# design.net
KiCad netlist of a schematic drawn in Altium Designer
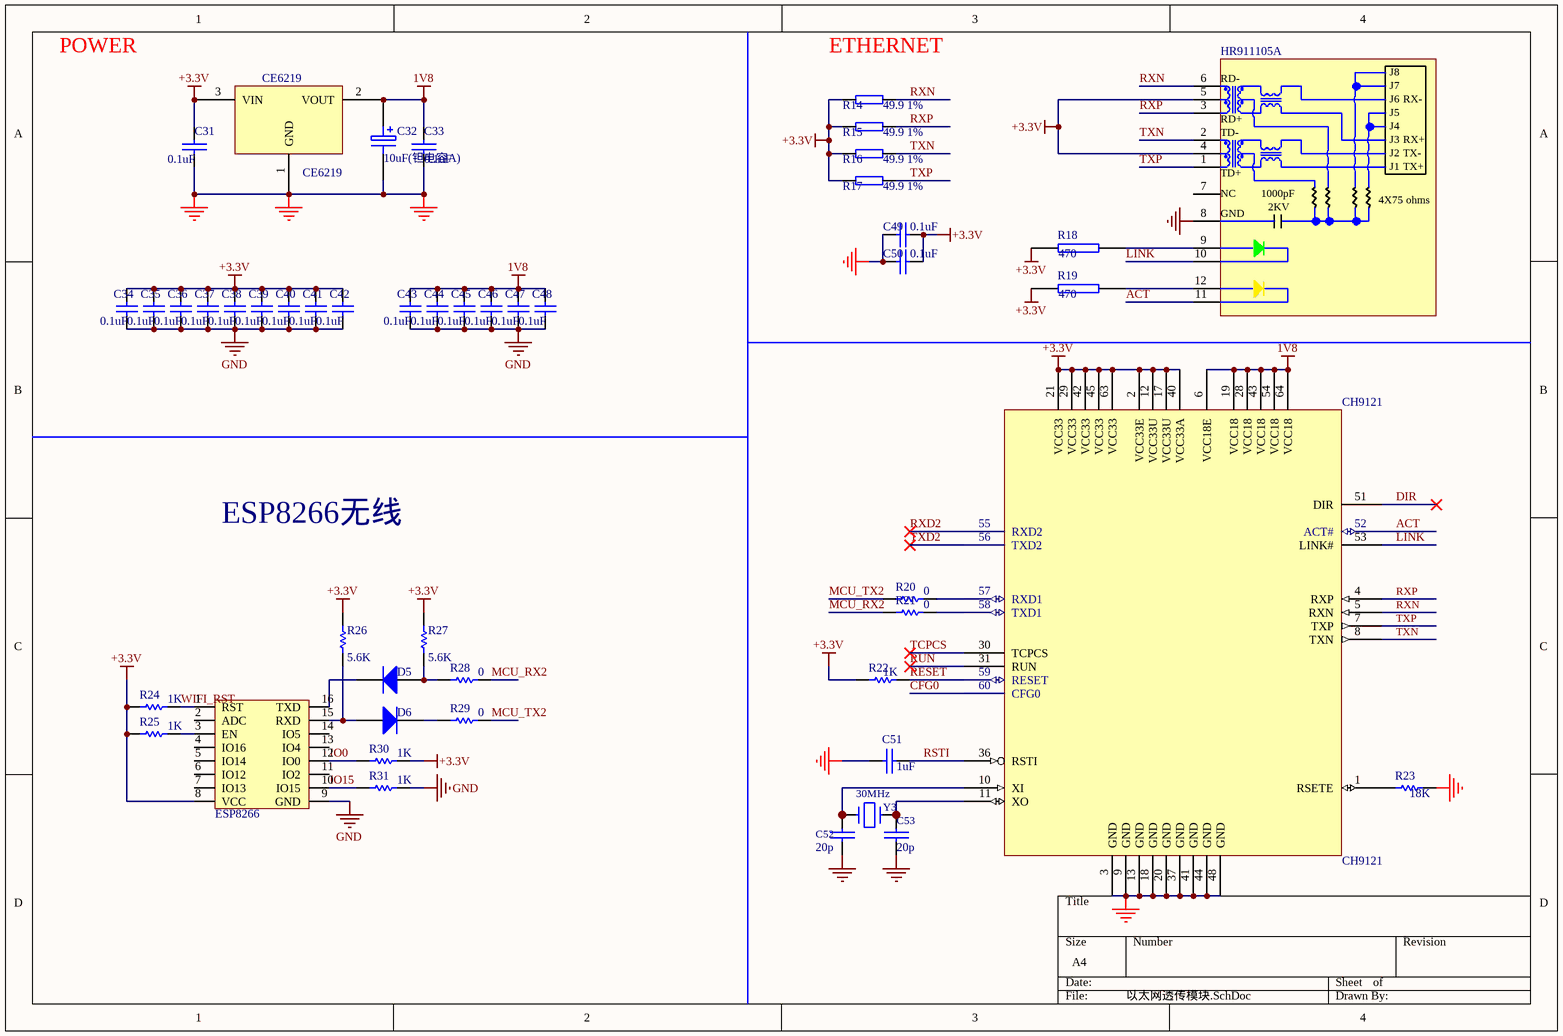
[diagram p0: 以太网透传模块.SchDoc]

(export (version "E")
  (design (tool "Eeschema 10.0.6"))
  (components
    (comp (ref "C31")
      (value "104")
      (footprint "0603")
      (description "Capacitor")
      (fields (field (name "ALTIUM_UNNAMED_1") "0.1uF"))
      (libsource (lib "*") (part "CAP"))
    )
    (comp (ref "C32")
      (value "10uF(钽电容A)")
      (footprint "钽电容(A)")
      (description "Electrolytic Capacitor")
      (libsource (lib "*") (part "ELECTRO1"))
    )
    (comp (ref "C33")
      (value "104")
      (footprint "0603")
      (description "Capacitor")
      (fields (field (name "ALTIUM_UNNAMED_1") "0.1uF"))
      (libsource (lib "*") (part "CAP"))
    )
    (comp (ref "C34")
      (value "0.1uF")
      (footprint "0603")
      (description "Capacitor")
      (fields (field (name "Comment") "104") (field (name "PUBLISHER") "Altium Limited"))
      (libsource (lib "Miscellaneous Devices") (part "Cap"))
    )
    (comp (ref "C35")
      (value "0.1uF")
      (footprint "0603")
      (description "Capacitor")
      (fields (field (name "Comment") "104") (field (name "PUBLISHER") "Altium Limited"))
      (libsource (lib "Miscellaneous Devices") (part "Cap"))
    )
    (comp (ref "C36")
      (value "0.1uF")
      (footprint "0603")
      (description "Capacitor")
      (fields (field (name "Comment") "104") (field (name "PUBLISHER") "Altium Limited"))
      (libsource (lib "Miscellaneous Devices") (part "Cap"))
    )
    (comp (ref "C37")
      (value "0.1uF")
      (footprint "0603")
      (description "Capacitor")
      (fields (field (name "Comment") "104") (field (name "PUBLISHER") "Altium Limited"))
      (libsource (lib "Miscellaneous Devices") (part "Cap"))
    )
    (comp (ref "C38")
      (value "0.1uF")
      (footprint "0603")
      (description "Capacitor")
      (fields (field (name "Comment") "104") (field (name "PUBLISHER") "Altium Limited"))
      (libsource (lib "Miscellaneous Devices") (part "Cap"))
    )
    (comp (ref "C39")
      (value "0.1uF")
      (footprint "0603")
      (description "Capacitor")
      (fields (field (name "Comment") "104") (field (name "PUBLISHER") "Altium Limited"))
      (libsource (lib "Miscellaneous Devices") (part "Cap"))
    )
    (comp (ref "C40")
      (value "0.1uF")
      (footprint "0603")
      (description "Capacitor")
      (fields (field (name "Comment") "104") (field (name "PUBLISHER") "Altium Limited"))
      (libsource (lib "Miscellaneous Devices") (part "Cap"))
    )
    (comp (ref "C41")
      (value "0.1uF")
      (footprint "0603")
      (description "Capacitor")
      (fields (field (name "Comment") "104") (field (name "PUBLISHER") "Altium Limited"))
      (libsource (lib "Miscellaneous Devices") (part "Cap"))
    )
    (comp (ref "C42")
      (value "0.1uF")
      (footprint "0603")
      (description "Capacitor")
      (fields (field (name "Comment") "104") (field (name "PUBLISHER") "Altium Limited"))
      (libsource (lib "Miscellaneous Devices") (part "Cap"))
    )
    (comp (ref "C43")
      (value "0.1uF")
      (footprint "0603")
      (description "Capacitor")
      (fields (field (name "Comment") "104") (field (name "PUBLISHER") "Altium Limited"))
      (libsource (lib "Miscellaneous Devices") (part "Cap"))
    )
    (comp (ref "C44")
      (value "0.1uF")
      (footprint "0603")
      (description "Capacitor")
      (fields (field (name "Comment") "104") (field (name "PUBLISHER") "Altium Limited"))
      (libsource (lib "Miscellaneous Devices") (part "Cap"))
    )
    (comp (ref "C45")
      (value "0.1uF")
      (footprint "0603")
      (description "Capacitor")
      (fields (field (name "Comment") "104") (field (name "PUBLISHER") "Altium Limited"))
      (libsource (lib "Miscellaneous Devices") (part "Cap"))
    )
    (comp (ref "C46")
      (value "0.1uF")
      (footprint "0603")
      (description "Capacitor")
      (fields (field (name "Comment") "104") (field (name "PUBLISHER") "Altium Limited"))
      (libsource (lib "Miscellaneous Devices") (part "Cap"))
    )
    (comp (ref "C47")
      (value "0.1uF")
      (footprint "0603")
      (description "Capacitor")
      (fields (field (name "Comment") "104") (field (name "PUBLISHER") "Altium Limited"))
      (libsource (lib "Miscellaneous Devices") (part "Cap"))
    )
    (comp (ref "C48")
      (value "0.1uF")
      (footprint "0603")
      (description "Capacitor")
      (fields (field (name "Comment") "104") (field (name "PUBLISHER") "Altium Limited"))
      (libsource (lib "Miscellaneous Devices") (part "Cap"))
    )
    (comp (ref "C49")
      (value "104")
      (footprint "0603")
      (description "Capacitor")
      (fields (field (name "ALTIUM_UNNAMED_1") "0.1uF"))
      (libsource (lib "*") (part "CAP"))
    )
    (comp (ref "C50")
      (value "104")
      (footprint "0603")
      (description "Capacitor")
      (fields (field (name "ALTIUM_UNNAMED_1") "0.1uF"))
      (libsource (lib "*") (part "CAP"))
    )
    (comp (ref "C51")
      (value "105")
      (footprint "0603")
      (description "Capacitor")
      (fields (field (name "ALTIUM_UNNAMED_1") "1uF"))
      (libsource (lib "*") (part "CAP"))
    )
    (comp (ref "C52")
      (value "20")
      (footprint "0603")
      (fields (field (name "ALTIUM_UNNAMED_1") "20p"))
      (libsource (lib "*") (part "Pro1BB.tmp_20p_7"))
    )
    (comp (ref "C53")
      (value "20")
      (footprint "0603")
      (fields (field (name "ALTIUM_UNNAMED_1") "20p"))
      (libsource (lib "*") (part "Pro1BB.tmp_20p_7"))
    )
    (comp (ref "CE6219") (value "CE6219") (footprint "SOT-23") (libsource (lib "*") (part "LM1117_3.3V")))
    (comp (ref "CH9121") (value "CH9121") (footprint "LQFP64_10x10") (libsource (lib "*") (part "CH9121")))
    (comp (ref "D5")
      (value "IN5819")
      (footprint "SOD-123")
      (description "1 Amp General Purpose Rectifier")
      (fields (field (name "PUBLISHER") "Altium Limited"))
      (libsource (lib "Miscellaneous Devices") (part "Diode 1N4001"))
    )
    (comp (ref "D6")
      (value "IN5819")
      (footprint "SOD-123")
      (description "1 Amp General Purpose Rectifier")
      (fields (field (name "PUBLISHER") "Altium Limited"))
      (libsource (lib "Miscellaneous Devices") (part "Diode 1N4001"))
    )
    (comp (ref "ESP8266")
      (value "ESP8266")
      (footprint "ESP8266")
      (libsource (lib "智能柜控制模块") (part "ESP8266"))
    )
    (comp (ref "HR911105A")
      (value "HR911105A")
      (footprint "HR911105A")
      (libsource (lib "*") (part "HR911105A"))
    )
    (comp (ref "R14")
      (value "49.9 1%")
      (footprint "0603")
      (fields (field (name "ALTIUM_UNNAMED_1") "49.9 1%"))
      (libsource (lib "*") (part "DZ"))
    )
    (comp (ref "R15")
      (value "49.9 1%")
      (footprint "0603")
      (fields (field (name "ALTIUM_UNNAMED_1") "49.9 1%"))
      (libsource (lib "*") (part "DZ"))
    )
    (comp (ref "R16")
      (value "49.9 1%")
      (footprint "0603")
      (fields (field (name "ALTIUM_UNNAMED_1") "49.9 1%"))
      (libsource (lib "*") (part "DZ"))
    )
    (comp (ref "R17")
      (value "49.9 1%")
      (footprint "0603")
      (fields (field (name "ALTIUM_UNNAMED_1") "49.9 1%"))
      (libsource (lib "*") (part "DZ"))
    )
    (comp (ref "R18")
      (value "470")
      (footprint "0603")
      (fields (field (name "ALTIUM_UNNAMED_1") "470"))
      (libsource (lib "*") (part "RES2"))
    )
    (comp (ref "R19")
      (value "470")
      (footprint "0603")
      (fields (field (name "ALTIUM_UNNAMED_1") "470"))
      (libsource (lib "*") (part "RES2"))
    )
    (comp (ref "R20")
      (value "0")
      (footprint "0603")
      (description "Resistor")
      (fields (field (name "PUBLISHER") "Altium Limited"))
      (libsource (lib "Miscellaneous Devices") (part "Res1"))
    )
    (comp (ref "R21")
      (value "0")
      (footprint "0603")
      (description "Resistor")
      (fields (field (name "PUBLISHER") "Altium Limited"))
      (libsource (lib "Miscellaneous Devices") (part "Res1"))
    )
    (comp (ref "R22")
      (value "1K")
      (footprint "0603")
      (description "Resistor")
      (fields (field (name "PUBLISHER") "Altium Limited"))
      (libsource (lib "Miscellaneous Devices") (part "Res1"))
    )
    (comp (ref "R23")
      (value "18K")
      (footprint "0603")
      (description "Resistor")
      (fields (field (name "PUBLISHER") "Altium Limited"))
      (libsource (lib "Miscellaneous Devices") (part "Res1"))
    )
    (comp (ref "R24")
      (value "1K")
      (footprint "0603")
      (description "Resistor")
      (fields (field (name "PUBLISHER") "Altium Limited"))
      (libsource (lib "Miscellaneous Devices") (part "Res1"))
    )
    (comp (ref "R25")
      (value "1K")
      (footprint "0603")
      (description "Resistor")
      (fields (field (name "PUBLISHER") "Altium Limited"))
      (libsource (lib "Miscellaneous Devices") (part "Res1"))
    )
    (comp (ref "R26")
      (value "5.6K")
      (footprint "0603")
      (description "Resistor")
      (fields (field (name "PUBLISHER") "Altium Limited"))
      (libsource (lib "Miscellaneous Devices") (part "Res1"))
    )
    (comp (ref "R27")
      (value "5.6K")
      (footprint "0603")
      (description "Resistor")
      (fields (field (name "PUBLISHER") "Altium Limited"))
      (libsource (lib "Miscellaneous Devices") (part "Res1"))
    )
    (comp (ref "R28")
      (value "0")
      (footprint "0603")
      (description "Resistor")
      (fields (field (name "PUBLISHER") "Altium Limited"))
      (libsource (lib "Miscellaneous Devices") (part "Res1"))
    )
    (comp (ref "R29")
      (value "0")
      (footprint "0603")
      (description "Resistor")
      (fields (field (name "PUBLISHER") "Altium Limited"))
      (libsource (lib "Miscellaneous Devices") (part "Res1"))
    )
    (comp (ref "R30")
      (value "1K")
      (footprint "0603")
      (description "Resistor")
      (fields (field (name "PUBLISHER") "Altium Limited"))
      (libsource (lib "Miscellaneous Devices") (part "Res1"))
    )
    (comp (ref "R31")
      (value "1K")
      (footprint "0603")
      (description "Resistor")
      (fields (field (name "PUBLISHER") "Altium Limited"))
      (libsource (lib "Miscellaneous Devices") (part "Res1"))
    )
    (comp (ref "Y3") (value "30MHz") (footprint "4025") (libsource (lib "*") (part "Pro1BB.tmp_12MHz_6")))
  )
  (nets
    (net (code "1") (name "+3.3V") (class "Default")
      (node (ref "C31") (pin "1") (pinfunction "1_1") (pintype "passive"))
      (node (ref "C34") (pin "1") (pinfunction "1_1") (pintype "passive"))
      (node (ref "C35") (pin "1") (pinfunction "1_1") (pintype "passive"))
      (node (ref "C36") (pin "1") (pinfunction "1_1") (pintype "passive"))
      (node (ref "C37") (pin "1") (pinfunction "1_1") (pintype "passive"))
      (node (ref "C38") (pin "1") (pinfunction "1_1") (pintype "passive"))
      (node (ref "C39") (pin "1") (pinfunction "1_1") (pintype "passive"))
      (node (ref "C40") (pin "1") (pinfunction "1_1") (pintype "passive"))
      (node (ref "C41") (pin "1") (pinfunction "1_1") (pintype "passive"))
      (node (ref "C42") (pin "1") (pinfunction "1_1") (pintype "passive"))
      (node (ref "C49") (pin "1") (pinfunction "1_1") (pintype "passive"))
      (node (ref "C50") (pin "1") (pinfunction "1_1") (pintype "passive"))
      (node (ref "CE6219") (pin "3") (pinfunction "VIN_3") (pintype "passive"))
      (node (ref "CH9121") (pin "12") (pinfunction "VCC33U_12") (pintype "power_in"))
      (node (ref "CH9121") (pin "17") (pinfunction "VCC33U_17") (pintype "power_in"))
      (node (ref "CH9121") (pin "2") (pinfunction "VCC33E_2") (pintype "power_in"))
      (node (ref "CH9121") (pin "21") (pinfunction "VCC33_21") (pintype "power_in"))
      (node (ref "CH9121") (pin "29") (pinfunction "VCC33_29") (pintype "power_in"))
      (node (ref "CH9121") (pin "40") (pinfunction "VCC33A_40") (pintype "power_in"))
      (node (ref "CH9121") (pin "42") (pinfunction "VCC33_42") (pintype "power_in"))
      (node (ref "CH9121") (pin "45") (pinfunction "VCC33_45") (pintype "power_in"))
      (node (ref "CH9121") (pin "63") (pinfunction "VCC33_63") (pintype "power_in"))
      (node (ref "ESP8266") (pin "8") (pinfunction "VCC_8") (pintype "passive"))
      (node (ref "HR911105A") (pin "4") (pintype "passive"))
      (node (ref "HR911105A") (pin "5") (pintype "passive"))
      (node (ref "R14") (pin "1") (pintype "passive"))
      (node (ref "R15") (pin "1") (pintype "passive"))
      (node (ref "R16") (pin "1") (pintype "passive"))
      (node (ref "R17") (pin "1") (pintype "passive"))
      (node (ref "R18") (pin "1") (pinfunction "1_1") (pintype "passive"))
      (node (ref "R19") (pin "1") (pinfunction "1_1") (pintype "passive"))
      (node (ref "R22") (pin "1") (pinfunction "1_1") (pintype "passive"))
      (node (ref "R24") (pin "1") (pinfunction "1_1") (pintype "passive"))
      (node (ref "R25") (pin "1") (pinfunction "1_1") (pintype "passive"))
      (node (ref "R26") (pin "2") (pinfunction "2_2") (pintype "passive"))
      (node (ref "R27") (pin "2") (pinfunction "2_2") (pintype "passive"))
      (node (ref "R30") (pin "2") (pinfunction "2_2") (pintype "passive"))
    )
    (net (code "2") (name "/ACT") (class "Default")
      (node (ref "CH9121") (pin "52") (pinfunction "ACT#_52") (pintype "bidirectional"))
      (node (ref "HR911105A") (pin "11") (pintype "passive"))
    )
    (net (code "3") (name "/CFG0") (class "Default")
      (node (ref "CH9121") (pin "60") (pinfunction "CFG0_60") (pintype "passive"))
    )
    (net (code "4") (name "/DIR") (class "Default")
      (node (ref "CH9121") (pin "51") (pinfunction "DIR_51") (pintype "passive+no_connect"))
    )
    (net (code "5") (name "/IO0") (class "Default")
      (node (ref "ESP8266") (pin "12") (pinfunction "IO0_12") (pintype "passive"))
      (node (ref "R30") (pin "1") (pinfunction "1_1") (pintype "passive"))
    )
    (net (code "6") (name "/IO15") (class "Default")
      (node (ref "ESP8266") (pin "10") (pinfunction "IO15_10") (pintype "passive"))
      (node (ref "R31") (pin "1") (pinfunction "1_1") (pintype "passive"))
    )
    (net (code "7") (name "/LINK") (class "Default")
      (node (ref "CH9121") (pin "53") (pinfunction "LINK#_53") (pintype "passive"))
      (node (ref "HR911105A") (pin "10") (pintype "passive"))
    )
    (net (code "8") (name "/MCU_RX2") (class "Default")
      (node (ref "R21") (pin "1") (pinfunction "1_1") (pintype "passive"))
      (node (ref "R28") (pin "2") (pinfunction "2_2") (pintype "passive"))
    )
    (net (code "9") (name "/MCU_TX2") (class "Default")
      (node (ref "R20") (pin "1") (pinfunction "1_1") (pintype "passive"))
      (node (ref "R29") (pin "2") (pinfunction "2_2") (pintype "passive"))
    )
    (net (code "10") (name "/RESET") (class "Default")
      (node (ref "CH9121") (pin "59") (pinfunction "RESET_59") (pintype "bidirectional"))
      (node (ref "R22") (pin "2") (pinfunction "2_2") (pintype "passive"))
    )
    (net (code "11") (name "/RSTI") (class "Default")
      (node (ref "C51") (pin "2") (pinfunction "2_2") (pintype "passive"))
      (node (ref "CH9121") (pin "36") (pinfunction "RSTI_36") (pintype "input"))
    )
    (net (code "12") (name "/RUN") (class "Default")
      (node (ref "CH9121") (pin "31") (pinfunction "RUN_31") (pintype "passive+no_connect"))
    )
    (net (code "13") (name "/RXD2") (class "Default")
      (node (ref "CH9121") (pin "55") (pinfunction "RXD2_55") (pintype "passive+no_connect"))
    )
    (net (code "14") (name "/RXN") (class "Default")
      (node (ref "CH9121") (pin "5") (pinfunction "RXN_5") (pintype "input"))
      (node (ref "HR911105A") (pin "6") (pintype "passive"))
      (node (ref "R14") (pin "2") (pintype "passive"))
    )
    (net (code "15") (name "/RXP") (class "Default")
      (node (ref "CH9121") (pin "4") (pinfunction "RXP_4") (pintype "input"))
      (node (ref "HR911105A") (pin "3") (pintype "passive"))
      (node (ref "R15") (pin "2") (pintype "passive"))
    )
    (net (code "16") (name "/TCPCS") (class "Default")
      (node (ref "CH9121") (pin "30") (pinfunction "TCPCS_30") (pintype "passive+no_connect"))
    )
    (net (code "17") (name "/TXD2") (class "Default")
      (node (ref "CH9121") (pin "56") (pinfunction "TXD2_56") (pintype "passive+no_connect"))
    )
    (net (code "18") (name "/TXN") (class "Default")
      (node (ref "CH9121") (pin "8") (pinfunction "TXN_8") (pintype "output"))
      (node (ref "HR911105A") (pin "2") (pintype "passive"))
      (node (ref "R16") (pin "2") (pintype "passive"))
    )
    (net (code "19") (name "/TXP") (class "Default")
      (node (ref "CH9121") (pin "7") (pinfunction "TXP_7") (pintype "output"))
      (node (ref "HR911105A") (pin "1") (pintype "passive"))
      (node (ref "R17") (pin "2") (pintype "passive"))
    )
    (net (code "20") (name "/WIFI_RST") (class "Default")
      (node (ref "ESP8266") (pin "1") (pinfunction "RST_1") (pintype "passive"))
      (node (ref "R24") (pin "2") (pinfunction "2_2") (pintype "passive"))
    )
    (net (code "21") (name "1V8") (class "Default")
      (node (ref "C32") (pin "1") (pinfunction "1_1") (pintype "passive"))
      (node (ref "C33") (pin "1") (pinfunction "1_1") (pintype "passive"))
      (node (ref "C43") (pin "1") (pinfunction "1_1") (pintype "passive"))
      (node (ref "C44") (pin "1") (pinfunction "1_1") (pintype "passive"))
      (node (ref "C45") (pin "1") (pinfunction "1_1") (pintype "passive"))
      (node (ref "C46") (pin "1") (pinfunction "1_1") (pintype "passive"))
      (node (ref "C47") (pin "1") (pinfunction "1_1") (pintype "passive"))
      (node (ref "C48") (pin "1") (pinfunction "1_1") (pintype "passive"))
      (node (ref "CE6219") (pin "2") (pinfunction "VOUT_2") (pintype "passive"))
      (node (ref "CH9121") (pin "19") (pinfunction "VCC18_19") (pintype "power_in"))
      (node (ref "CH9121") (pin "28") (pinfunction "VCC18_28") (pintype "power_in"))
      (node (ref "CH9121") (pin "43") (pinfunction "VCC18_43") (pintype "power_in"))
      (node (ref "CH9121") (pin "54") (pinfunction "VCC18_54") (pintype "power_in"))
      (node (ref "CH9121") (pin "6") (pinfunction "VCC18E_6") (pintype "power_in"))
      (node (ref "CH9121") (pin "64") (pinfunction "VCC18_64") (pintype "power_in"))
    )
    (net (code "22") (name "GND") (class "Default")
      (node (ref "C31") (pin "2") (pinfunction "2_2") (pintype "passive"))
      (node (ref "C32") (pin "2") (pinfunction "2_2") (pintype "passive"))
      (node (ref "C33") (pin "2") (pinfunction "2_2") (pintype "passive"))
      (node (ref "C34") (pin "2") (pinfunction "2_2") (pintype "passive"))
      (node (ref "C35") (pin "2") (pinfunction "2_2") (pintype "passive"))
      (node (ref "C36") (pin "2") (pinfunction "2_2") (pintype "passive"))
      (node (ref "C37") (pin "2") (pinfunction "2_2") (pintype "passive"))
      (node (ref "C38") (pin "2") (pinfunction "2_2") (pintype "passive"))
      (node (ref "C39") (pin "2") (pinfunction "2_2") (pintype "passive"))
      (node (ref "C40") (pin "2") (pinfunction "2_2") (pintype "passive"))
      (node (ref "C41") (pin "2") (pinfunction "2_2") (pintype "passive"))
      (node (ref "C42") (pin "2") (pinfunction "2_2") (pintype "passive"))
      (node (ref "C43") (pin "2") (pinfunction "2_2") (pintype "passive"))
      (node (ref "C44") (pin "2") (pinfunction "2_2") (pintype "passive"))
      (node (ref "C45") (pin "2") (pinfunction "2_2") (pintype "passive"))
      (node (ref "C46") (pin "2") (pinfunction "2_2") (pintype "passive"))
      (node (ref "C47") (pin "2") (pinfunction "2_2") (pintype "passive"))
      (node (ref "C48") (pin "2") (pinfunction "2_2") (pintype "passive"))
      (node (ref "C49") (pin "2") (pinfunction "2_2") (pintype "passive"))
      (node (ref "C50") (pin "2") (pinfunction "2_2") (pintype "passive"))
      (node (ref "C51") (pin "1") (pinfunction "1_1") (pintype "passive"))
      (node (ref "C52") (pin "2") (pintype "passive"))
      (node (ref "C53") (pin "2") (pintype "passive"))
      (node (ref "CE6219") (pin "1") (pinfunction "GND_1") (pintype "passive"))
      (node (ref "CH9121") (pin "13") (pinfunction "GND_13") (pintype "power_in"))
      (node (ref "CH9121") (pin "18") (pinfunction "GND_18") (pintype "power_in"))
      (node (ref "CH9121") (pin "20") (pinfunction "GND_20") (pintype "power_in"))
      (node (ref "CH9121") (pin "3") (pinfunction "GND_3") (pintype "power_in"))
      (node (ref "CH9121") (pin "37") (pinfunction "GND_37") (pintype "power_in"))
      (node (ref "CH9121") (pin "41") (pinfunction "GND_41") (pintype "power_in"))
      (node (ref "CH9121") (pin "44") (pinfunction "GND_44") (pintype "power_in"))
      (node (ref "CH9121") (pin "48") (pinfunction "GND_48") (pintype "power_in"))
      (node (ref "CH9121") (pin "9") (pinfunction "GND_9") (pintype "power_in"))
      (node (ref "ESP8266") (pin "9") (pinfunction "GND_9") (pintype "passive"))
      (node (ref "HR911105A") (pin "8") (pintype "passive"))
      (node (ref "R23") (pin "2") (pinfunction "2_2") (pintype "passive"))
      (node (ref "R31") (pin "2") (pinfunction "2_2") (pintype "passive"))
    )
    (net (code "23") (name "Net-(CH9121-RSETE)") (class "Default")
      (node (ref "CH9121") (pin "1") (pinfunction "RSETE_1") (pintype "bidirectional"))
      (node (ref "R23") (pin "1") (pinfunction "1_1") (pintype "passive"))
    )
    (net (code "24") (name "Net-(CH9121-RXD1)") (class "Default")
      (node (ref "CH9121") (pin "57") (pinfunction "RXD1_57") (pintype "bidirectional"))
      (node (ref "R20") (pin "2") (pinfunction "2_2") (pintype "passive"))
    )
    (net (code "25") (name "Net-(CH9121-TXD1)") (class "Default")
      (node (ref "CH9121") (pin "58") (pinfunction "TXD1_58") (pintype "bidirectional"))
      (node (ref "R21") (pin "2") (pinfunction "2_2") (pintype "passive"))
    )
    (net (code "26") (name "Net-(CH9121-XI)") (class "Default")
      (node (ref "C52") (pin "1") (pintype "passive"))
      (node (ref "CH9121") (pin "10") (pinfunction "XI_10") (pintype "input"))
      (node (ref "Y3") (pin "1") (pintype "passive"))
    )
    (net (code "27") (name "Net-(CH9121-XO)") (class "Default")
      (node (ref "C53") (pin "1") (pintype "passive"))
      (node (ref "CH9121") (pin "11") (pinfunction "XO_11") (pintype "bidirectional"))
      (node (ref "Y3") (pin "2") (pintype "passive"))
    )
    (net (code "28") (name "Net-(D5-A)") (class "Default")
      (node (ref "D5") (pin "1") (pinfunction "A_1") (pintype "passive"))
      (node (ref "R27") (pin "1") (pinfunction "1_1") (pintype "passive"))
      (node (ref "R28") (pin "1") (pinfunction "1_1") (pintype "passive"))
    )
    (net (code "29") (name "Net-(D5-K)") (class "Default")
      (node (ref "D5") (pin "2") (pinfunction "K_2") (pintype "passive"))
      (node (ref "ESP8266") (pin "16") (pinfunction "TXD_16") (pintype "passive"))
    )
    (net (code "30") (name "Net-(D6-A)") (class "Default")
      (node (ref "D6") (pin "1") (pinfunction "A_1") (pintype "passive"))
      (node (ref "ESP8266") (pin "15") (pinfunction "RXD_15") (pintype "passive"))
      (node (ref "R26") (pin "1") (pinfunction "1_1") (pintype "passive"))
    )
    (net (code "31") (name "Net-(D6-K)") (class "Default")
      (node (ref "D6") (pin "2") (pinfunction "K_2") (pintype "passive"))
      (node (ref "R29") (pin "1") (pinfunction "1_1") (pintype "passive"))
    )
    (net (code "32") (name "Net-(ESP8266-EN)") (class "Default")
      (node (ref "ESP8266") (pin "3") (pinfunction "EN_3") (pintype "passive"))
      (node (ref "R25") (pin "2") (pinfunction "2_2") (pintype "passive"))
    )
    (net (code "33") (name "Net-(HR911105A-Pad9)") (class "Default")
      (node (ref "HR911105A") (pin "9") (pintype "passive"))
      (node (ref "R18") (pin "2") (pinfunction "2_2") (pintype "passive"))
    )
    (net (code "34") (name "Net-(HR911105A-Pad12)") (class "Default")
      (node (ref "HR911105A") (pin "12") (pintype "passive"))
      (node (ref "R19") (pin "2") (pinfunction "2_2") (pintype "passive"))
    )
    (net (code "35") (name "unconnected-(ESP8266-ADC-Pad2)") (class "Default")
      (node (ref "ESP8266") (pin "2") (pinfunction "ADC_2") (pintype "passive"))
    )
    (net (code "36") (name "unconnected-(ESP8266-IO2-Pad11)") (class "Default")
      (node (ref "ESP8266") (pin "11") (pinfunction "IO2_11") (pintype "passive"))
    )
    (net (code "37") (name "unconnected-(ESP8266-IO4-Pad13)") (class "Default")
      (node (ref "ESP8266") (pin "13") (pinfunction "IO4_13") (pintype "passive"))
    )
    (net (code "38") (name "unconnected-(ESP8266-IO5-Pad14)") (class "Default")
      (node (ref "ESP8266") (pin "14") (pinfunction "IO5_14") (pintype "passive"))
    )
    (net (code "39") (name "unconnected-(ESP8266-IO12-Pad6)") (class "Default")
      (node (ref "ESP8266") (pin "6") (pinfunction "IO12_6") (pintype "passive"))
    )
    (net (code "40") (name "unconnected-(ESP8266-IO13-Pad7)") (class "Default")
      (node (ref "ESP8266") (pin "7") (pinfunction "IO13_7") (pintype "passive"))
    )
    (net (code "41") (name "unconnected-(ESP8266-IO14-Pad5)") (class "Default")
      (node (ref "ESP8266") (pin "5") (pinfunction "IO14_5") (pintype "passive"))
    )
    (net (code "42") (name "unconnected-(ESP8266-IO16-Pad4)") (class "Default")
      (node (ref "ESP8266") (pin "4") (pinfunction "IO16_4") (pintype "passive"))
    )
    (net (code "43") (name "unconnected-(HR911105A-Pad7)") (class "Default")
      (node (ref "HR911105A") (pin "7") (pintype "passive"))
    )
  )
)
